# Lattice.net
KiCad netlist of a schematic drawn in EAGLE
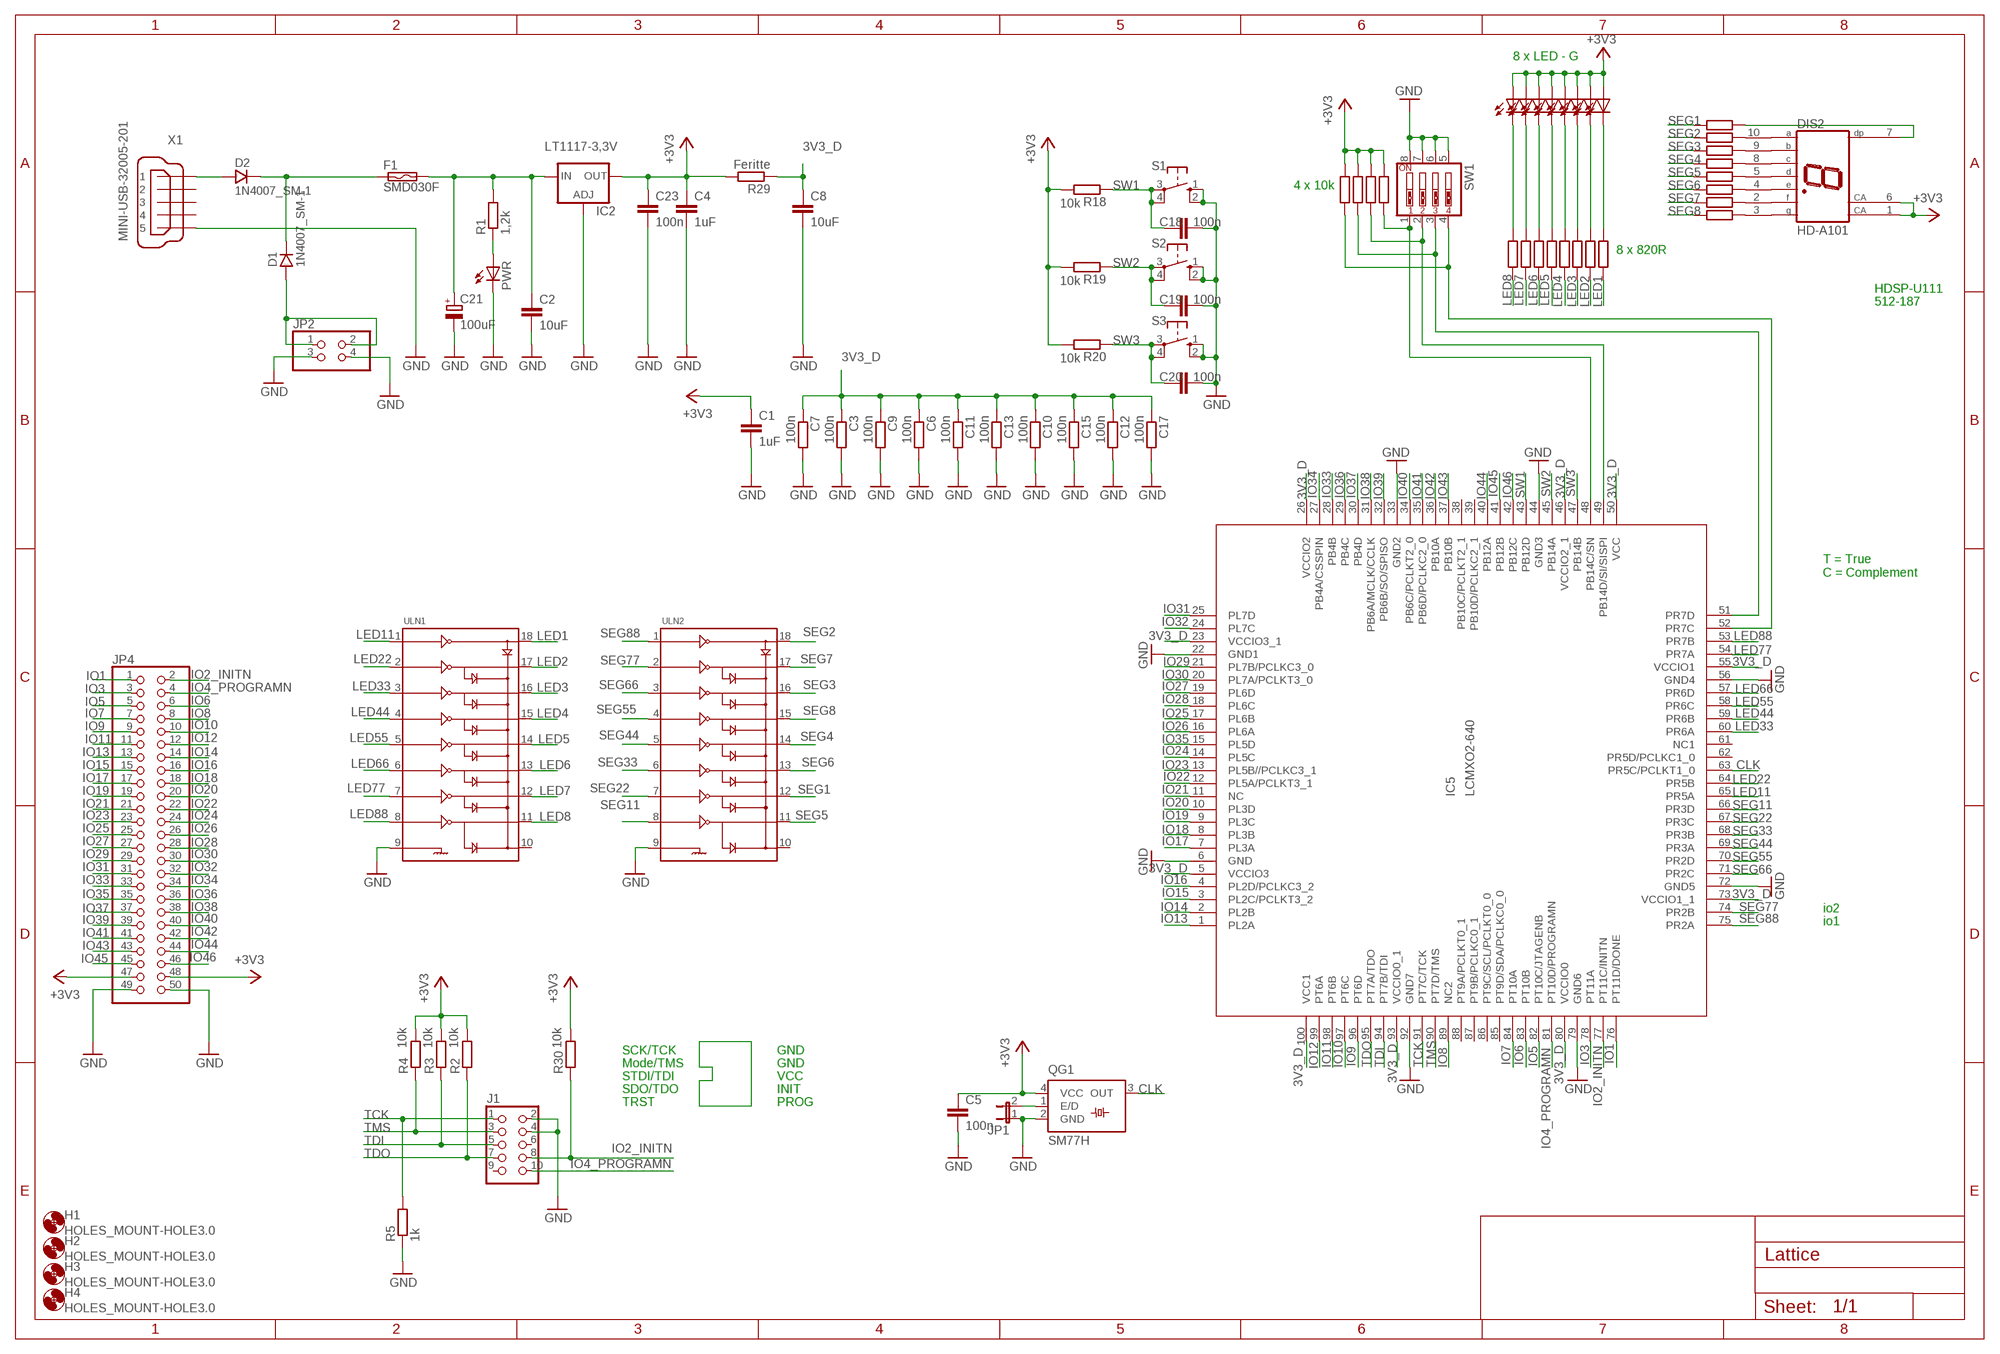
[diagram p0: schematic, sheet 1]

(export (version "E")
  (design (tool "Eeschema 10.0.6"))
  (components
    (comp (ref "C1")
      (value "1uF")
      (footprint "eagle-import:C1206")
      (libsource (lib "eagle-import") (part "C-EUC1206"))
    )
    (comp (ref "C2")
      (value "10uF")
      (footprint "eagle-import:C1206")
      (libsource (lib "eagle-import") (part "C-EUC1206"))
    )
    (comp (ref "C3")
      (value "100n")
      (footprint "eagle-import:R0603")
      (libsource (lib "eagle-import") (part "R-EU_R0603"))
    )
    (comp (ref "C4")
      (value "1uF")
      (footprint "eagle-import:C1206")
      (libsource (lib "eagle-import") (part "C-EUC1206"))
    )
    (comp (ref "C5")
      (value "100n")
      (footprint "eagle-import:C0805")
      (libsource (lib "eagle-import") (part "C-EUC0805"))
    )
    (comp (ref "C6")
      (value "100n")
      (footprint "eagle-import:R0603")
      (libsource (lib "eagle-import") (part "R-EU_R0603"))
    )
    (comp (ref "C7")
      (value "100n")
      (footprint "eagle-import:R0603")
      (libsource (lib "eagle-import") (part "R-EU_R0603"))
    )
    (comp (ref "C8")
      (value "10uF")
      (footprint "eagle-import:C1206")
      (libsource (lib "eagle-import") (part "C-EUC1206"))
    )
    (comp (ref "C9")
      (value "100n")
      (footprint "eagle-import:R0603")
      (libsource (lib "eagle-import") (part "R-EU_R0603"))
    )
    (comp (ref "C10")
      (value "100n")
      (footprint "eagle-import:R0603")
      (libsource (lib "eagle-import") (part "R-EU_R0603"))
    )
    (comp (ref "C11")
      (value "100n")
      (footprint "eagle-import:R0603")
      (libsource (lib "eagle-import") (part "R-EU_R0603"))
    )
    (comp (ref "C12")
      (value "100n")
      (footprint "eagle-import:R0603")
      (libsource (lib "eagle-import") (part "R-EU_R0603"))
    )
    (comp (ref "C13")
      (value "100n")
      (footprint "eagle-import:R0603")
      (libsource (lib "eagle-import") (part "R-EU_R0603"))
    )
    (comp (ref "C15")
      (value "100n")
      (footprint "eagle-import:R0603")
      (libsource (lib "eagle-import") (part "R-EU_R0603"))
    )
    (comp (ref "C17")
      (value "100n")
      (footprint "eagle-import:R0603")
      (libsource (lib "eagle-import") (part "R-EU_R0603"))
    )
    (comp (ref "C18")
      (value "100n")
      (footprint "eagle-import:C0805")
      (libsource (lib "eagle-import") (part "C-EUC0805"))
    )
    (comp (ref "C19")
      (value "100n")
      (footprint "eagle-import:C0805")
      (libsource (lib "eagle-import") (part "C-EUC0805"))
    )
    (comp (ref "C20")
      (value "100n")
      (footprint "eagle-import:C0805")
      (libsource (lib "eagle-import") (part "C-EUC0805"))
    )
    (comp (ref "C21")
      (value "100uF")
      (footprint "eagle-import:153CLV-0605")
      (libsource (lib "eagle-import") (part "CPOL-EU153CLV-0605"))
    )
    (comp (ref "C23")
      (value "100n")
      (footprint "eagle-import:C0805")
      (libsource (lib "eagle-import") (part "C-EUC0805"))
    )
    (comp (ref "D1")
      (value "1N4007_SM-1")
      (footprint "eagle-import:SM-1")
      (libsource (lib "eagle-import") (part "1N4007_SM-1"))
    )
    (comp (ref "D2")
      (value "1N4007_SM-1")
      (footprint "eagle-import:SM-1")
      (libsource (lib "eagle-import") (part "1N4007_SM-1"))
    )
    (comp (ref "DIS2")
      (value "HD-A101")
      (footprint "eagle-import:HDSP-A")
      (libsource (lib "eagle-import") (part "HD-A101"))
    )
    (comp (ref "F1")
      (value "SMD030F")
      (footprint "eagle-import:SMD050F")
      (libsource (lib "eagle-import") (part "SMDF030"))
    )
    (comp (ref "H1")
      (value "HOLES_MOUNT-HOLE3.0")
      (footprint "eagle-import:HOLES_3,0")
      (libsource (lib "eagle-import") (part "HOLES_MOUNT-HOLE3.0"))
    )
    (comp (ref "H2")
      (value "HOLES_MOUNT-HOLE3.0")
      (footprint "eagle-import:HOLES_3,0")
      (libsource (lib "eagle-import") (part "HOLES_MOUNT-HOLE3.0"))
    )
    (comp (ref "H3")
      (value "HOLES_MOUNT-HOLE3.0")
      (footprint "eagle-import:HOLES_3,0")
      (libsource (lib "eagle-import") (part "HOLES_MOUNT-HOLE3.0"))
    )
    (comp (ref "H4")
      (value "HOLES_MOUNT-HOLE3.0")
      (footprint "eagle-import:HOLES_3,0")
      (libsource (lib "eagle-import") (part "HOLES_MOUNT-HOLE3.0"))
    )
    (comp (ref "IC2")
      (value "LT1117-3,3V")
      (footprint "eagle-import:SOT223")
      (libsource (lib "eagle-import") (part "LD117A?S50TR"))
    )
    (comp (ref "IC5")
      (value "LCMXO2-640")
      (footprint "eagle-import:LCMX02-640")
      (libsource (lib "eagle-import") (part "LXMXO2-640"))
    )
    (comp (ref "J1")
      (value "CON_HEADER_2X05-PTH+SHROUDED_A")
      (footprint "eagle-import:PINSHRD_PTH_2X05")
      (libsource (lib "eagle-import") (part "CON_HEADER_2X05-PTH+SHROUDED_A"))
    )
    (comp (ref "JP1")
      (value "JP1E")
      (footprint "eagle-import:JP1")
      (libsource (lib "eagle-import") (part "JP1E"))
    )
    (comp (ref "JP2")
      (value "PINHD-2X2")
      (footprint "eagle-import:2X02")
      (libsource (lib "eagle-import") (part "PINHD-2X2"))
    )
    (comp (ref "JP4")
      (value "PINHD-2X25")
      (footprint "eagle-import:2X25")
      (libsource (lib "eagle-import") (part "PINHD-2X25"))
    )
    (comp (ref "LED1")
      (value "LEDSMT1206")
      (footprint "eagle-import:1206")
      (libsource (lib "eagle-import") (part "LEDSMT1206"))
    )
    (comp (ref "LED2")
      (value "LEDSMT1206")
      (footprint "eagle-import:1206")
      (libsource (lib "eagle-import") (part "LEDSMT1206"))
    )
    (comp (ref "LED3")
      (value "LEDSMT1206")
      (footprint "eagle-import:1206")
      (libsource (lib "eagle-import") (part "LEDSMT1206"))
    )
    (comp (ref "LED4")
      (value "LEDSMT1206")
      (footprint "eagle-import:1206")
      (libsource (lib "eagle-import") (part "LEDSMT1206"))
    )
    (comp (ref "LED5")
      (value "LEDSMT1206")
      (footprint "eagle-import:1206")
      (libsource (lib "eagle-import") (part "LEDSMT1206"))
    )
    (comp (ref "LED6")
      (value "LEDSMT1206")
      (footprint "eagle-import:1206")
      (libsource (lib "eagle-import") (part "LEDSMT1206"))
    )
    (comp (ref "LED7")
      (value "LEDSMT1206")
      (footprint "eagle-import:1206")
      (libsource (lib "eagle-import") (part "LEDSMT1206"))
    )
    (comp (ref "LED8")
      (value "LEDSMT1206")
      (footprint "eagle-import:1206")
      (libsource (lib "eagle-import") (part "LEDSMT1206"))
    )
    (comp (ref "PWR")
      (value "LEDSMT1206")
      (footprint "eagle-import:1206")
      (libsource (lib "eagle-import") (part "LEDSMT1206"))
    )
    (comp (ref "QG1")
      (value "SM77H")
      (footprint "eagle-import:SM77H")
      (libsource (lib "eagle-import") (part "SM77H"))
    )
    (comp (ref "R1")
      (value "1,2k")
      (footprint "eagle-import:R0805")
      (libsource (lib "eagle-import") (part "rcl_R-EU_R0805"))
    )
    (comp (ref "R2")
      (value "10k")
      (footprint "eagle-import:R0805")
      (libsource (lib "eagle-import") (part "rcl_R-EU_R0805"))
    )
    (comp (ref "R3")
      (value "10k")
      (footprint "eagle-import:R0805")
      (libsource (lib "eagle-import") (part "rcl_R-EU_R0805"))
    )
    (comp (ref "R4")
      (value "10k")
      (footprint "eagle-import:R0805")
      (libsource (lib "eagle-import") (part "rcl_R-EU_R0805"))
    )
    (comp (ref "R5")
      (value "1k")
      (footprint "eagle-import:R0805")
      (libsource (lib "eagle-import") (part "rcl_R-EU_R0805"))
    )
    (comp (ref "R6")
      (value "R-EU_R0805")
      (footprint "eagle-import:R0805")
      (libsource (lib "eagle-import") (part "rcl_R-EU_R0805"))
    )
    (comp (ref "R7")
      (value "R-EU_R0805")
      (footprint "eagle-import:R0805")
      (libsource (lib "eagle-import") (part "rcl_R-EU_R0805"))
    )
    (comp (ref "R8")
      (value "R-EU_R0805")
      (footprint "eagle-import:R0805")
      (libsource (lib "eagle-import") (part "rcl_R-EU_R0805"))
    )
    (comp (ref "R9")
      (value "R-EU_R0805")
      (footprint "eagle-import:R0805")
      (libsource (lib "eagle-import") (part "rcl_R-EU_R0805"))
    )
    (comp (ref "R10")
      (value "R-EU_R0805")
      (footprint "eagle-import:R0805")
      (libsource (lib "eagle-import") (part "rcl_R-EU_R0805"))
    )
    (comp (ref "R11")
      (value "R-EU_R0805")
      (footprint "eagle-import:R0805")
      (libsource (lib "eagle-import") (part "rcl_R-EU_R0805"))
    )
    (comp (ref "R12")
      (value "R-EU_R0805")
      (footprint "eagle-import:R0805")
      (libsource (lib "eagle-import") (part "rcl_R-EU_R0805"))
    )
    (comp (ref "R13")
      (value "R-EU_R0805")
      (footprint "eagle-import:R0805")
      (libsource (lib "eagle-import") (part "rcl_R-EU_R0805"))
    )
    (comp (ref "R14")
      (value "R-EU_R0805")
      (footprint "eagle-import:R0805")
      (libsource (lib "eagle-import") (part "rcl_R-EU_R0805"))
    )
    (comp (ref "R15")
      (value "R-EU_R0805")
      (footprint "eagle-import:R0805")
      (libsource (lib "eagle-import") (part "rcl_R-EU_R0805"))
    )
    (comp (ref "R16")
      (value "R-EU_R0805")
      (footprint "eagle-import:R0805")
      (libsource (lib "eagle-import") (part "rcl_R-EU_R0805"))
    )
    (comp (ref "R17")
      (value "R-EU_R0805")
      (footprint "eagle-import:R0805")
      (libsource (lib "eagle-import") (part "rcl_R-EU_R0805"))
    )
    (comp (ref "R18")
      (value "10k")
      (footprint "eagle-import:R0805")
      (libsource (lib "eagle-import") (part "rcl_R-EU_R0805"))
    )
    (comp (ref "R19")
      (value "10k")
      (footprint "eagle-import:R0805")
      (libsource (lib "eagle-import") (part "rcl_R-EU_R0805"))
    )
    (comp (ref "R20")
      (value "10k")
      (footprint "eagle-import:R0805")
      (libsource (lib "eagle-import") (part "rcl_R-EU_R0805"))
    )
    (comp (ref "R21")
      (value "R-EU_R0805")
      (footprint "eagle-import:R0805")
      (libsource (lib "eagle-import") (part "rcl_R-EU_R0805"))
    )
    (comp (ref "R22")
      (value "R-EU_R0805")
      (footprint "eagle-import:R0805")
      (libsource (lib "eagle-import") (part "rcl_R-EU_R0805"))
    )
    (comp (ref "R23")
      (value "R-EU_R0805")
      (footprint "eagle-import:R0805")
      (libsource (lib "eagle-import") (part "rcl_R-EU_R0805"))
    )
    (comp (ref "R24")
      (value "R-EU_R0805")
      (footprint "eagle-import:R0805")
      (libsource (lib "eagle-import") (part "rcl_R-EU_R0805"))
    )
    (comp (ref "R25")
      (value "R-EU_R0805")
      (footprint "eagle-import:R0805")
      (libsource (lib "eagle-import") (part "rcl_R-EU_R0805"))
    )
    (comp (ref "R26")
      (value "R-EU_R0805")
      (footprint "eagle-import:R0805")
      (libsource (lib "eagle-import") (part "rcl_R-EU_R0805"))
    )
    (comp (ref "R27")
      (value "R-EU_R0805")
      (footprint "eagle-import:R0805")
      (libsource (lib "eagle-import") (part "rcl_R-EU_R0805"))
    )
    (comp (ref "R28")
      (value "R-EU_R0805")
      (footprint "eagle-import:R0805")
      (libsource (lib "eagle-import") (part "rcl_R-EU_R0805"))
    )
    (comp (ref "R29")
      (value "Feritte")
      (footprint "eagle-import:R0805")
      (libsource (lib "eagle-import") (part "rcl_R-EU_R0805"))
    )
    (comp (ref "R30")
      (value "10k")
      (footprint "eagle-import:R0805")
      (libsource (lib "eagle-import") (part "rcl_R-EU_R0805"))
    )
    (comp (ref "S1")
      (value "10-XX")
      (footprint "eagle-import:B3F-10XX")
      (fields (field (name "MPN") "B3F-1000"))
      (libsource (lib "eagle-import") (part "10-XX"))
    )
    (comp (ref "S2")
      (value "10-XX")
      (footprint "eagle-import:B3F-10XX")
      (fields (field (name "MPN") "B3F-1000"))
      (libsource (lib "eagle-import") (part "10-XX"))
    )
    (comp (ref "S3")
      (value "10-XX")
      (footprint "eagle-import:B3F-10XX")
      (fields (field (name "MPN") "B3F-1000"))
      (libsource (lib "eagle-import") (part "10-XX"))
    )
    (comp (ref "SW1")
      (value "SW_DIP-4")
      (footprint "eagle-import:EDG-04")
      (libsource (lib "eagle-import") (part "SW_DIP-4"))
    )
    (comp (ref "ULN1")
      (value "ULN2803SOIC")
      (footprint "eagle-import:SO018")
      (libsource (lib "eagle-import") (part "ULN2803SOIC"))
    )
    (comp (ref "ULN2")
      (value "ULN2803SOIC")
      (footprint "eagle-import:SO018")
      (libsource (lib "eagle-import") (part "ULN2803SOIC"))
    )
    (comp (ref "X1")
      (value "MINI-USB-32005-201")
      (footprint "eagle-import:32005-201")
      (libsource (lib "eagle-import") (part "MINI-USB-32005-201"))
    )
  )
  (nets
    (net (code "1") (name "+3V3") (class "Default")
      (node (ref "C1") (pin "1") (pinfunction "1_1") (pintype "passive"))
      (node (ref "C23") (pin "1") (pinfunction "1_1") (pintype "passive"))
      (node (ref "C4") (pin "1") (pinfunction "1_1") (pintype "passive"))
      (node (ref "C5") (pin "1") (pinfunction "1_1") (pintype "passive"))
      (node (ref "DIS2") (pin "1") (pinfunction "CA_1") (pintype "passive"))
      (node (ref "DIS2") (pin "6") (pinfunction "CA_6") (pintype "passive"))
      (node (ref "IC2") (pin "4") (pinfunction "OUT_4") (pintype "passive"))
      (node (ref "JP4") (pin "47") (pinfunction "47_47") (pintype "passive"))
      (node (ref "JP4") (pin "48") (pinfunction "48_48") (pintype "passive"))
      (node (ref "LED1") (pin "A") (pinfunction "A_A") (pintype "passive"))
      (node (ref "LED2") (pin "A") (pinfunction "A_A") (pintype "passive"))
      (node (ref "LED3") (pin "A") (pinfunction "A_A") (pintype "passive"))
      (node (ref "LED4") (pin "A") (pinfunction "A_A") (pintype "passive"))
      (node (ref "LED5") (pin "A") (pinfunction "A_A") (pintype "passive"))
      (node (ref "LED6") (pin "A") (pinfunction "A_A") (pintype "passive"))
      (node (ref "LED7") (pin "A") (pinfunction "A_A") (pintype "passive"))
      (node (ref "LED8") (pin "A") (pinfunction "A_A") (pintype "passive"))
      (node (ref "QG1") (pin "4") (pinfunction "VCC_4") (pintype "power_in"))
      (node (ref "R14") (pin "1") (pinfunction "1_1") (pintype "passive"))
      (node (ref "R15") (pin "1") (pinfunction "1_1") (pintype "passive"))
      (node (ref "R16") (pin "1") (pinfunction "1_1") (pintype "passive"))
      (node (ref "R17") (pin "1") (pinfunction "1_1") (pintype "passive"))
      (node (ref "R18") (pin "2") (pinfunction "2_2") (pintype "passive"))
      (node (ref "R19") (pin "2") (pinfunction "2_2") (pintype "passive"))
      (node (ref "R2") (pin "2") (pinfunction "2_2") (pintype "passive"))
      (node (ref "R20") (pin "2") (pinfunction "2_2") (pintype "passive"))
      (node (ref "R29") (pin "2") (pinfunction "2_2") (pintype "passive"))
      (node (ref "R3") (pin "2") (pinfunction "2_2") (pintype "passive"))
      (node (ref "R30") (pin "2") (pinfunction "2_2") (pintype "passive"))
      (node (ref "R4") (pin "2") (pinfunction "2_2") (pintype "passive"))
    )
    (net (code "2") (name "/3V3_D") (class "Default")
      (node (ref "C10") (pin "1") (pinfunction "1_1") (pintype "passive"))
      (node (ref "C11") (pin "1") (pinfunction "1_1") (pintype "passive"))
      (node (ref "C12") (pin "1") (pinfunction "1_1") (pintype "passive"))
      (node (ref "C13") (pin "1") (pinfunction "1_1") (pintype "passive"))
      (node (ref "C15") (pin "1") (pinfunction "1_1") (pintype "passive"))
      (node (ref "C17") (pin "1") (pinfunction "1_1") (pintype "passive"))
      (node (ref "C3") (pin "1") (pinfunction "1_1") (pintype "passive"))
      (node (ref "C6") (pin "1") (pinfunction "1_1") (pintype "passive"))
      (node (ref "C7") (pin "1") (pinfunction "1_1") (pintype "passive"))
      (node (ref "C8") (pin "1") (pinfunction "1_1") (pintype "passive"))
      (node (ref "C9") (pin "1") (pinfunction "1_1") (pintype "passive"))
      (node (ref "IC5") (pin "100") (pinfunction "VCC1_100") (pintype "power_in"))
      (node (ref "IC5") (pin "23") (pinfunction "VCCIO3_1_23") (pintype "power_in"))
      (node (ref "IC5") (pin "26") (pinfunction "VCCIO2_26") (pintype "power_in"))
      (node (ref "IC5") (pin "46") (pinfunction "VCCIO2_1_46") (pintype "power_in"))
      (node (ref "IC5") (pin "5") (pinfunction "VCCIO3_5") (pintype "power_in"))
      (node (ref "IC5") (pin "50") (pinfunction "VCC_50") (pintype "power_in"))
      (node (ref "IC5") (pin "55") (pinfunction "VCCIO1_55") (pintype "power_in"))
      (node (ref "IC5") (pin "73") (pinfunction "VCCIO1_1_73") (pintype "power_in"))
      (node (ref "IC5") (pin "80") (pinfunction "VCCIO0_80") (pintype "power_in"))
      (node (ref "IC5") (pin "93") (pinfunction "VCCIO0_1_93") (pintype "power_in"))
      (node (ref "R29") (pin "1") (pinfunction "1_1") (pintype "passive"))
    )
    (net (code "3") (name "/CLK") (class "Default")
      (node (ref "IC5") (pin "63") (pinfunction "PR5C/PCLKT1_0_63") (pintype "bidirectional"))
      (node (ref "QG1") (pin "3") (pinfunction "OUT_3") (pintype "output"))
    )
    (net (code "4") (name "/IO1") (class "Default")
      (node (ref "IC5") (pin "76") (pinfunction "PT11D/DONE_76") (pintype "bidirectional"))
      (node (ref "JP4") (pin "1") (pinfunction "1_1") (pintype "passive"))
    )
    (net (code "5") (name "/IO2_INITN") (class "Default")
      (node (ref "IC5") (pin "77") (pinfunction "PT11C/INITN_77") (pintype "bidirectional"))
      (node (ref "J1") (pin "8") (pinfunction "8_8") (pintype "passive"))
      (node (ref "JP4") (pin "2") (pinfunction "2_2") (pintype "passive"))
      (node (ref "R30") (pin "1") (pinfunction "1_1") (pintype "passive"))
    )
    (net (code "6") (name "/IO3") (class "Default")
      (node (ref "IC5") (pin "78") (pinfunction "PT11A_78") (pintype "bidirectional"))
      (node (ref "JP4") (pin "3") (pinfunction "3_3") (pintype "passive"))
    )
    (net (code "7") (name "/IO4_PROGRAMN") (class "Default")
      (node (ref "IC5") (pin "81") (pinfunction "PT10D/PROGRAMN_81") (pintype "bidirectional"))
      (node (ref "J1") (pin "10") (pinfunction "10_10") (pintype "passive"))
      (node (ref "JP4") (pin "4") (pinfunction "4_4") (pintype "passive"))
    )
    (net (code "8") (name "/IO5") (class "Default")
      (node (ref "IC5") (pin "82") (pinfunction "PT10C/JTAGENB_82") (pintype "bidirectional"))
      (node (ref "JP4") (pin "5") (pinfunction "5_5") (pintype "passive"))
    )
    (net (code "9") (name "/IO6") (class "Default")
      (node (ref "IC5") (pin "83") (pinfunction "PT10B_83") (pintype "bidirectional"))
      (node (ref "JP4") (pin "6") (pinfunction "6_6") (pintype "passive"))
    )
    (net (code "10") (name "/IO7") (class "Default")
      (node (ref "IC5") (pin "84") (pinfunction "PT10A_84") (pintype "bidirectional"))
      (node (ref "JP4") (pin "7") (pinfunction "7_7") (pintype "passive"))
    )
    (net (code "11") (name "/IO8") (class "Default")
      (node (ref "IC5") (pin "89") (pinfunction "NC2_89") (pintype "bidirectional"))
      (node (ref "JP4") (pin "8") (pinfunction "8_8") (pintype "passive"))
    )
    (net (code "12") (name "/IO9") (class "Default")
      (node (ref "IC5") (pin "96") (pinfunction "PT6D_96") (pintype "bidirectional"))
      (node (ref "JP4") (pin "9") (pinfunction "9_9") (pintype "passive"))
    )
    (net (code "13") (name "/IO10") (class "Default")
      (node (ref "IC5") (pin "97") (pinfunction "PT6C_97") (pintype "bidirectional"))
      (node (ref "JP4") (pin "10") (pinfunction "10_10") (pintype "passive"))
    )
    (net (code "14") (name "/IO11") (class "Default")
      (node (ref "IC5") (pin "98") (pinfunction "PT6B_98") (pintype "bidirectional"))
      (node (ref "JP4") (pin "11") (pinfunction "11_11") (pintype "passive"))
    )
    (net (code "15") (name "/IO12") (class "Default")
      (node (ref "IC5") (pin "99") (pinfunction "PT6A_99") (pintype "bidirectional"))
      (node (ref "JP4") (pin "12") (pinfunction "12_12") (pintype "passive"))
    )
    (net (code "16") (name "/IO13") (class "Default")
      (node (ref "IC5") (pin "1") (pinfunction "PL2A_1") (pintype "input"))
      (node (ref "JP4") (pin "13") (pinfunction "13_13") (pintype "passive"))
    )
    (net (code "17") (name "/IO14") (class "Default")
      (node (ref "IC5") (pin "2") (pinfunction "PL2B_2") (pintype "bidirectional"))
      (node (ref "JP4") (pin "14") (pinfunction "14_14") (pintype "passive"))
    )
    (net (code "18") (name "/IO15") (class "Default")
      (node (ref "IC5") (pin "3") (pinfunction "PL2C/PCLKT3_2_3") (pintype "bidirectional"))
      (node (ref "JP4") (pin "15") (pinfunction "15_15") (pintype "passive"))
    )
    (net (code "19") (name "/IO16") (class "Default")
      (node (ref "IC5") (pin "4") (pinfunction "PL2D/PCLKC3_2_4") (pintype "bidirectional"))
      (node (ref "JP4") (pin "16") (pinfunction "16_16") (pintype "passive"))
    )
    (net (code "20") (name "/IO17") (class "Default")
      (node (ref "IC5") (pin "7") (pinfunction "PL3A_7") (pintype "bidirectional"))
      (node (ref "JP4") (pin "17") (pinfunction "17_17") (pintype "passive"))
    )
    (net (code "21") (name "/IO18") (class "Default")
      (node (ref "IC5") (pin "8") (pinfunction "PL3B_8") (pintype "bidirectional"))
      (node (ref "JP4") (pin "18") (pinfunction "18_18") (pintype "passive"))
    )
    (net (code "22") (name "/IO19") (class "Default")
      (node (ref "IC5") (pin "9") (pinfunction "PL3C_9") (pintype "bidirectional"))
      (node (ref "JP4") (pin "19") (pinfunction "19_19") (pintype "passive"))
    )
    (net (code "23") (name "/IO20") (class "Default")
      (node (ref "IC5") (pin "10") (pinfunction "PL3D_10") (pintype "bidirectional"))
      (node (ref "JP4") (pin "20") (pinfunction "20_20") (pintype "passive"))
    )
    (net (code "24") (name "/IO21") (class "Default")
      (node (ref "IC5") (pin "11") (pinfunction "NC_11") (pintype "bidirectional"))
      (node (ref "JP4") (pin "21") (pinfunction "21_21") (pintype "passive"))
    )
    (net (code "25") (name "/IO22") (class "Default")
      (node (ref "IC5") (pin "12") (pinfunction "PL5A/PCLKT3_1_12") (pintype "bidirectional"))
      (node (ref "JP4") (pin "22") (pinfunction "22_22") (pintype "passive"))
    )
    (net (code "26") (name "/IO23") (class "Default")
      (node (ref "IC5") (pin "13") (pinfunction "PL5B//PCLKC3_1_13") (pintype "bidirectional"))
      (node (ref "JP4") (pin "23") (pinfunction "23_23") (pintype "passive"))
    )
    (net (code "27") (name "/IO24") (class "Default")
      (node (ref "IC5") (pin "14") (pinfunction "PL5C_14") (pintype "bidirectional"))
      (node (ref "JP4") (pin "24") (pinfunction "24_24") (pintype "passive"))
    )
    (net (code "28") (name "/IO25") (class "Default")
      (node (ref "IC5") (pin "17") (pinfunction "PL6B_17") (pintype "bidirectional"))
      (node (ref "JP4") (pin "25") (pinfunction "25_25") (pintype "passive"))
    )
    (net (code "29") (name "/IO26") (class "Default")
      (node (ref "IC5") (pin "16") (pinfunction "PL6A_16") (pintype "bidirectional"))
      (node (ref "JP4") (pin "26") (pinfunction "26_26") (pintype "passive"))
    )
    (net (code "30") (name "/IO27") (class "Default")
      (node (ref "IC5") (pin "19") (pinfunction "PL6D_19") (pintype "bidirectional"))
      (node (ref "JP4") (pin "27") (pinfunction "27_27") (pintype "passive"))
    )
    (net (code "31") (name "/IO28") (class "Default")
      (node (ref "IC5") (pin "18") (pinfunction "PL6C_18") (pintype "bidirectional"))
      (node (ref "JP4") (pin "28") (pinfunction "28_28") (pintype "passive"))
    )
    (net (code "32") (name "/IO29") (class "Default")
      (node (ref "IC5") (pin "21") (pinfunction "PL7B/PCLKC3_0_21") (pintype "bidirectional"))
      (node (ref "JP4") (pin "29") (pinfunction "29_29") (pintype "passive"))
    )
    (net (code "33") (name "/IO30") (class "Default")
      (node (ref "IC5") (pin "20") (pinfunction "PL7A/PCLKT3_0_20") (pintype "bidirectional"))
      (node (ref "JP4") (pin "30") (pinfunction "30_30") (pintype "passive"))
    )
    (net (code "34") (name "/IO31") (class "Default")
      (node (ref "IC5") (pin "25") (pinfunction "PL7D_25") (pintype "bidirectional"))
      (node (ref "JP4") (pin "31") (pinfunction "31_31") (pintype "passive"))
    )
    (net (code "35") (name "/IO32") (class "Default")
      (node (ref "IC5") (pin "24") (pinfunction "PL7C_24") (pintype "bidirectional"))
      (node (ref "JP4") (pin "32") (pinfunction "32_32") (pintype "passive"))
    )
    (net (code "36") (name "/IO33") (class "Default")
      (node (ref "IC5") (pin "28") (pinfunction "PB4B_28") (pintype "bidirectional"))
      (node (ref "JP4") (pin "33") (pinfunction "33_33") (pintype "passive"))
    )
    (net (code "37") (name "/IO34") (class "Default")
      (node (ref "IC5") (pin "27") (pinfunction "PB4A/CSSPIN_27") (pintype "bidirectional"))
      (node (ref "JP4") (pin "34") (pinfunction "34_34") (pintype "passive"))
    )
    (net (code "38") (name "/IO35") (class "Default")
      (node (ref "IC5") (pin "15") (pinfunction "PL5D_15") (pintype "bidirectional"))
      (node (ref "JP4") (pin "35") (pinfunction "35_35") (pintype "passive"))
    )
    (net (code "39") (name "/IO36") (class "Default")
      (node (ref "IC5") (pin "29") (pinfunction "PB4C_29") (pintype "bidirectional"))
      (node (ref "JP4") (pin "36") (pinfunction "36_36") (pintype "passive"))
    )
    (net (code "40") (name "/IO37") (class "Default")
      (node (ref "IC5") (pin "30") (pinfunction "PB4D_30") (pintype "bidirectional"))
      (node (ref "JP4") (pin "37") (pinfunction "37_37") (pintype "passive"))
    )
    (net (code "41") (name "/IO38") (class "Default")
      (node (ref "IC5") (pin "31") (pinfunction "PB6A/MCLK/CCLK_31") (pintype "bidirectional"))
      (node (ref "JP4") (pin "38") (pinfunction "38_38") (pintype "passive"))
    )
    (net (code "42") (name "/IO39") (class "Default")
      (node (ref "IC5") (pin "32") (pinfunction "PB6B/SO/SPISO_32") (pintype "bidirectional"))
      (node (ref "JP4") (pin "39") (pinfunction "39_39") (pintype "passive"))
    )
    (net (code "43") (name "/IO40") (class "Default")
      (node (ref "IC5") (pin "34") (pinfunction "PB6C/PCLKT2_0_34") (pintype "bidirectional"))
      (node (ref "JP4") (pin "40") (pinfunction "40_40") (pintype "passive"))
    )
    (net (code "44") (name "/IO41") (class "Default")
      (node (ref "IC5") (pin "35") (pinfunction "PB6D/PCLKC2_0_35") (pintype "bidirectional"))
      (node (ref "JP4") (pin "41") (pinfunction "41_41") (pintype "passive"))
    )
    (net (code "45") (name "/IO42") (class "Default")
      (node (ref "IC5") (pin "36") (pinfunction "PB10A_36") (pintype "bidirectional"))
      (node (ref "JP4") (pin "42") (pinfunction "42_42") (pintype "passive"))
    )
    (net (code "46") (name "/IO43") (class "Default")
      (node (ref "IC5") (pin "37") (pinfunction "PB10B_37") (pintype "bidirectional"))
      (node (ref "JP4") (pin "43") (pinfunction "43_43") (pintype "passive"))
    )
    (net (code "47") (name "/IO44") (class "Default")
      (node (ref "IC5") (pin "40") (pinfunction "PB12A_40") (pintype "bidirectional"))
      (node (ref "JP4") (pin "44") (pinfunction "44_44") (pintype "passive"))
    )
    (net (code "48") (name "/IO45") (class "Default")
      (node (ref "IC5") (pin "41") (pinfunction "PB12B_41") (pintype "bidirectional"))
      (node (ref "JP4") (pin "45") (pinfunction "45_45") (pintype "passive"))
    )
    (net (code "49") (name "/IO46") (class "Default")
      (node (ref "IC5") (pin "42") (pinfunction "PB12C_42") (pintype "bidirectional"))
      (node (ref "JP4") (pin "46") (pinfunction "46_46") (pintype "passive"))
    )
    (net (code "50") (name "/LED1") (class "Default")
      (node (ref "R6") (pin "1") (pinfunction "1_1") (pintype "passive"))
      (node (ref "ULN1") (pin "18") (pinfunction "18_18") (pintype "bidirectional"))
    )
    (net (code "51") (name "/LED2") (class "Default")
      (node (ref "R7") (pin "1") (pinfunction "1_1") (pintype "passive"))
      (node (ref "ULN1") (pin "17") (pinfunction "17_17") (pintype "bidirectional"))
    )
    (net (code "52") (name "/LED3") (class "Default")
      (node (ref "R8") (pin "1") (pinfunction "1_1") (pintype "passive"))
      (node (ref "ULN1") (pin "16") (pinfunction "16_16") (pintype "bidirectional"))
    )
    (net (code "53") (name "/LED4") (class "Default")
      (node (ref "R9") (pin "1") (pinfunction "1_1") (pintype "passive"))
      (node (ref "ULN1") (pin "15") (pinfunction "15_15") (pintype "bidirectional"))
    )
    (net (code "54") (name "/LED5") (class "Default")
      (node (ref "R10") (pin "1") (pinfunction "1_1") (pintype "passive"))
      (node (ref "ULN1") (pin "14") (pinfunction "14_14") (pintype "bidirectional"))
    )
    (net (code "55") (name "/LED6") (class "Default")
      (node (ref "R11") (pin "1") (pinfunction "1_1") (pintype "passive"))
      (node (ref "ULN1") (pin "13") (pinfunction "13_13") (pintype "bidirectional"))
    )
    (net (code "56") (name "/LED7") (class "Default")
      (node (ref "R12") (pin "1") (pinfunction "1_1") (pintype "passive"))
      (node (ref "ULN1") (pin "12") (pinfunction "12_12") (pintype "bidirectional"))
    )
    (net (code "57") (name "/LED8") (class "Default")
      (node (ref "R13") (pin "1") (pinfunction "1_1") (pintype "passive"))
      (node (ref "ULN1") (pin "11") (pinfunction "11_11") (pintype "bidirectional"))
    )
    (net (code "58") (name "/LED11") (class "Default")
      (node (ref "IC5") (pin "65") (pinfunction "PR5A_65") (pintype "bidirectional"))
      (node (ref "ULN1") (pin "1") (pinfunction "1_1") (pintype "bidirectional"))
    )
    (net (code "59") (name "/LED22") (class "Default")
      (node (ref "IC5") (pin "64") (pinfunction "PR5B_64") (pintype "bidirectional"))
      (node (ref "ULN1") (pin "2") (pinfunction "2_2") (pintype "bidirectional"))
    )
    (net (code "60") (name "/LED33") (class "Default")
      (node (ref "IC5") (pin "60") (pinfunction "PR6A_60") (pintype "bidirectional"))
      (node (ref "ULN1") (pin "3") (pinfunction "3_3") (pintype "bidirectional"))
    )
    (net (code "61") (name "/LED44") (class "Default")
      (node (ref "IC5") (pin "59") (pinfunction "PR6B_59") (pintype "bidirectional"))
      (node (ref "ULN1") (pin "4") (pinfunction "4_4") (pintype "bidirectional"))
    )
    (net (code "62") (name "/LED55") (class "Default")
      (node (ref "IC5") (pin "58") (pinfunction "PR6C_58") (pintype "bidirectional"))
      (node (ref "ULN1") (pin "5") (pinfunction "5_5") (pintype "bidirectional"))
    )
    (net (code "63") (name "/LED66") (class "Default")
      (node (ref "IC5") (pin "57") (pinfunction "PR6D_57") (pintype "bidirectional"))
      (node (ref "ULN1") (pin "6") (pinfunction "6_6") (pintype "bidirectional"))
    )
    (net (code "64") (name "/LED77") (class "Default")
      (node (ref "IC5") (pin "54") (pinfunction "PR7A_54") (pintype "bidirectional"))
      (node (ref "ULN1") (pin "7") (pinfunction "7_7") (pintype "bidirectional"))
    )
    (net (code "65") (name "/LED88") (class "Default")
      (node (ref "IC5") (pin "53") (pinfunction "PR7B_53") (pintype "bidirectional"))
      (node (ref "ULN1") (pin "8") (pinfunction "8_8") (pintype "bidirectional"))
    )
    (net (code "66") (name "/SEG1") (class "Default")
      (node (ref "R21") (pin "2") (pinfunction "2_2") (pintype "passive"))
      (node (ref "ULN2") (pin "12") (pinfunction "12_12") (pintype "bidirectional"))
    )
    (net (code "67") (name "/SEG2") (class "Default")
      (node (ref "R22") (pin "2") (pinfunction "2_2") (pintype "passive"))
      (node (ref "ULN2") (pin "18") (pinfunction "18_18") (pintype "bidirectional"))
    )
    (net (code "68") (name "/SEG3") (class "Default")
      (node (ref "R23") (pin "2") (pinfunction "2_2") (pintype "passive"))
      (node (ref "ULN2") (pin "16") (pinfunction "16_16") (pintype "bidirectional"))
    )
    (net (code "69") (name "/SEG4") (class "Default")
      (node (ref "R24") (pin "2") (pinfunction "2_2") (pintype "passive"))
      (node (ref "ULN2") (pin "14") (pinfunction "14_14") (pintype "bidirectional"))
    )
    (net (code "70") (name "/SEG5") (class "Default")
      (node (ref "R25") (pin "2") (pinfunction "2_2") (pintype "passive"))
      (node (ref "ULN2") (pin "11") (pinfunction "11_11") (pintype "bidirectional"))
    )
    (net (code "71") (name "/SEG6") (class "Default")
      (node (ref "R26") (pin "2") (pinfunction "2_2") (pintype "passive"))
      (node (ref "ULN2") (pin "13") (pinfunction "13_13") (pintype "bidirectional"))
    )
    (net (code "72") (name "/SEG7") (class "Default")
      (node (ref "R27") (pin "2") (pinfunction "2_2") (pintype "passive"))
      (node (ref "ULN2") (pin "17") (pinfunction "17_17") (pintype "bidirectional"))
    )
    (net (code "73") (name "/SEG8") (class "Default")
      (node (ref "R28") (pin "2") (pinfunction "2_2") (pintype "passive"))
      (node (ref "ULN2") (pin "15") (pinfunction "15_15") (pintype "bidirectional"))
    )
    (net (code "74") (name "/SEG11") (class "Default")
      (node (ref "IC5") (pin "66") (pinfunction "PR3D_66") (pintype "bidirectional"))
      (node (ref "ULN2") (pin "8") (pinfunction "8_8") (pintype "bidirectional"))
    )
    (net (code "75") (name "/SEG22") (class "Default")
      (node (ref "IC5") (pin "67") (pinfunction "PR3C_67") (pintype "bidirectional"))
      (node (ref "ULN2") (pin "7") (pinfunction "7_7") (pintype "bidirectional"))
    )
    (net (code "76") (name "/SEG33") (class "Default")
      (node (ref "IC5") (pin "68") (pinfunction "PR3B_68") (pintype "bidirectional"))
      (node (ref "ULN2") (pin "6") (pinfunction "6_6") (pintype "bidirectional"))
    )
    (net (code "77") (name "/SEG44") (class "Default")
      (node (ref "IC5") (pin "69") (pinfunction "PR3A_69") (pintype "bidirectional"))
      (node (ref "ULN2") (pin "5") (pinfunction "5_5") (pintype "bidirectional"))
    )
    (net (code "78") (name "/SEG55") (class "Default")
      (node (ref "IC5") (pin "70") (pinfunction "PR2D_70") (pintype "bidirectional"))
      (node (ref "ULN2") (pin "4") (pinfunction "4_4") (pintype "bidirectional"))
    )
    (net (code "79") (name "/SEG66") (class "Default")
      (node (ref "IC5") (pin "71") (pinfunction "PR2C_71") (pintype "bidirectional"))
      (node (ref "ULN2") (pin "3") (pinfunction "3_3") (pintype "bidirectional"))
    )
    (net (code "80") (name "/SEG77") (class "Default")
      (node (ref "IC5") (pin "74") (pinfunction "PR2B_74") (pintype "bidirectional"))
      (node (ref "ULN2") (pin "2") (pinfunction "2_2") (pintype "bidirectional"))
    )
    (net (code "81") (name "/SEG88") (class "Default")
      (node (ref "IC5") (pin "75") (pinfunction "PR2A_75") (pintype "bidirectional"))
      (node (ref "ULN2") (pin "1") (pinfunction "1_1") (pintype "bidirectional"))
    )
    (net (code "82") (name "/SW1") (class "Default")
      (node (ref "C18") (pin "1") (pinfunction "1_1") (pintype "passive"))
      (node (ref "IC5") (pin "43") (pinfunction "PB12D_43") (pintype "bidirectional"))
      (node (ref "R18") (pin "1") (pinfunction "1_1") (pintype "passive"))
      (node (ref "S1") (pin "3") (pinfunction "P_3") (pintype "passive"))
      (node (ref "S1") (pin "4") (pinfunction "P1_4") (pintype "passive"))
    )
    (net (code "83") (name "/SW2") (class "Default")
      (node (ref "C19") (pin "1") (pinfunction "1_1") (pintype "passive"))
      (node (ref "IC5") (pin "45") (pinfunction "PB14A_45") (pintype "bidirectional"))
      (node (ref "R19") (pin "1") (pinfunction "1_1") (pintype "passive"))
      (node (ref "S2") (pin "3") (pinfunction "P_3") (pintype "passive"))
      (node (ref "S2") (pin "4") (pinfunction "P1_4") (pintype "passive"))
    )
    (net (code "84") (name "/SW3") (class "Default")
      (node (ref "C20") (pin "1") (pinfunction "1_1") (pintype "passive"))
      (node (ref "IC5") (pin "47") (pinfunction "PB14B_47") (pintype "bidirectional"))
      (node (ref "R20") (pin "1") (pinfunction "1_1") (pintype "passive"))
      (node (ref "S3") (pin "3") (pinfunction "P_3") (pintype "passive"))
      (node (ref "S3") (pin "4") (pinfunction "P1_4") (pintype "passive"))
    )
    (net (code "85") (name "/TCK") (class "Default")
      (node (ref "IC5") (pin "91") (pinfunction "PT7C/TCK_91") (pintype "bidirectional"))
      (node (ref "J1") (pin "1") (pinfunction "1_1") (pintype "passive"))
      (node (ref "R5") (pin "2") (pinfunction "2_2") (pintype "passive"))
    )
    (net (code "86") (name "/TDI") (class "Default")
      (node (ref "IC5") (pin "94") (pinfunction "PT7B/TDI_94") (pintype "bidirectional"))
      (node (ref "J1") (pin "5") (pinfunction "5_5") (pintype "passive"))
      (node (ref "R3") (pin "1") (pinfunction "1_1") (pintype "passive"))
    )
    (net (code "87") (name "/TDO") (class "Default")
      (node (ref "IC5") (pin "95") (pinfunction "PT7A/TDO_95") (pintype "bidirectional"))
      (node (ref "J1") (pin "7") (pinfunction "7_7") (pintype "passive"))
      (node (ref "R2") (pin "1") (pinfunction "1_1") (pintype "passive"))
    )
    (net (code "88") (name "/TMS") (class "Default")
      (node (ref "IC5") (pin "90") (pinfunction "PT7D/TMS_90") (pintype "bidirectional"))
      (node (ref "J1") (pin "3") (pinfunction "3_3") (pintype "passive"))
      (node (ref "R4") (pin "1") (pinfunction "1_1") (pintype "passive"))
    )
    (net (code "89") (name "GND") (class "Default")
      (node (ref "C1") (pin "2") (pinfunction "2_2") (pintype "passive"))
      (node (ref "C10") (pin "2") (pinfunction "2_2") (pintype "passive"))
      (node (ref "C11") (pin "2") (pinfunction "2_2") (pintype "passive"))
      (node (ref "C12") (pin "2") (pinfunction "2_2") (pintype "passive"))
      (node (ref "C13") (pin "2") (pinfunction "2_2") (pintype "passive"))
      (node (ref "C15") (pin "2") (pinfunction "2_2") (pintype "passive"))
      (node (ref "C17") (pin "2") (pinfunction "2_2") (pintype "passive"))
      (node (ref "C18") (pin "2") (pinfunction "2_2") (pintype "passive"))
      (node (ref "C19") (pin "2") (pinfunction "2_2") (pintype "passive"))
      (node (ref "C2") (pin "2") (pinfunction "2_2") (pintype "passive"))
      (node (ref "C20") (pin "2") (pinfunction "2_2") (pintype "passive"))
      (node (ref "C21") (pin "-") (pinfunction "-_-") (pintype "passive"))
      (node (ref "C23") (pin "2") (pinfunction "2_2") (pintype "passive"))
      (node (ref "C3") (pin "2") (pinfunction "2_2") (pintype "passive"))
      (node (ref "C4") (pin "2") (pinfunction "2_2") (pintype "passive"))
      (node (ref "C5") (pin "2") (pinfunction "2_2") (pintype "passive"))
      (node (ref "C6") (pin "2") (pinfunction "2_2") (pintype "passive"))
      (node (ref "C7") (pin "2") (pinfunction "2_2") (pintype "passive"))
      (node (ref "C8") (pin "2") (pinfunction "2_2") (pintype "passive"))
      (node (ref "C9") (pin "2") (pinfunction "2_2") (pintype "passive"))
      (node (ref "IC2") (pin "1") (pinfunction "ADJ_1") (pintype "input"))
      (node (ref "IC5") (pin "22") (pinfunction "GND1_22") (pintype "power_in"))
      (node (ref "IC5") (pin "33") (pinfunction "GND2_33") (pintype "power_in"))
      (node (ref "IC5") (pin "44") (pinfunction "GND3_44") (pintype "power_in"))
      (node (ref "IC5") (pin "56") (pinfunction "GND4_56") (pintype "power_in"))
      (node (ref "IC5") (pin "6") (pinfunction "GND_6") (pintype "power_in"))
      (node (ref "IC5") (pin "72") (pinfunction "GND5_72") (pintype "power_in"))
      (node (ref "IC5") (pin "79") (pinfunction "GND6_79") (pintype "power_in"))
      (node (ref "IC5") (pin "92") (pinfunction "GND7_92") (pintype "power_in"))
      (node (ref "J1") (pin "2") (pinfunction "2_2") (pintype "passive"))
      (node (ref "J1") (pin "4") (pinfunction "4_4") (pintype "passive"))
      (node (ref "JP1") (pin "1") (pinfunction "1_1") (pintype "passive"))
      (node (ref "JP2") (pin "3") (pinfunction "3_3") (pintype "passive"))
      (node (ref "JP2") (pin "4") (pinfunction "4_4") (pintype "passive"))
      (node (ref "JP4") (pin "49") (pinfunction "49_49") (pintype "passive"))
      (node (ref "JP4") (pin "50") (pinfunction "50_50") (pintype "passive"))
      (node (ref "PWR") (pin "C") (pinfunction "C_C") (pintype "passive"))
      (node (ref "QG1") (pin "2") (pinfunction "GND_2") (pintype "power_in"))
      (node (ref "R5") (pin "1") (pinfunction "1_1") (pintype "passive"))
      (node (ref "S1") (pin "1") (pinfunction "S_1") (pintype "passive"))
      (node (ref "S1") (pin "2") (pinfunction "S1_2") (pintype "passive"))
      (node (ref "S2") (pin "1") (pinfunction "S_1") (pintype "passive"))
      (node (ref "S2") (pin "2") (pinfunction "S1_2") (pintype "passive"))
      (node (ref "S3") (pin "1") (pinfunction "S_1") (pintype "passive"))
      (node (ref "S3") (pin "2") (pinfunction "S1_2") (pintype "passive"))
      (node (ref "SW1") (pin "5") (pinfunction "5_5") (pintype "passive"))
      (node (ref "SW1") (pin "6") (pinfunction "6_6") (pintype "passive"))
      (node (ref "SW1") (pin "7") (pinfunction "7_7") (pintype "passive"))
      (node (ref "SW1") (pin "8") (pinfunction "8_8") (pintype "passive"))
      (node (ref "ULN1") (pin "9") (pinfunction "9_9") (pintype "bidirectional"))
      (node (ref "ULN2") (pin "9") (pinfunction "9_9") (pintype "bidirectional"))
      (node (ref "X1") (pin "5") (pinfunction "5_5") (pintype "passive"))
    )
    (net (code "90") (name "Net-(D1-PadA)") (class "Default")
      (node (ref "D1") (pin "A") (pinfunction "A_A") (pintype "passive"))
      (node (ref "JP2") (pin "1") (pinfunction "1_1") (pintype "passive"))
      (node (ref "JP2") (pin "2") (pinfunction "2_2") (pintype "passive"))
    )
    (net (code "91") (name "Net-(D1-PadK)") (class "Default")
      (node (ref "D1") (pin "K") (pinfunction "K_K") (pintype "passive"))
      (node (ref "D2") (pin "K") (pinfunction "K_K") (pintype "passive"))
      (node (ref "F1") (pin "1") (pinfunction "1_1") (pintype "passive"))
    )
    (net (code "92") (name "Net-(D2-PadA)") (class "Default")
      (node (ref "D2") (pin "A") (pinfunction "A_A") (pintype "passive"))
      (node (ref "X1") (pin "1") (pinfunction "1_1") (pintype "passive"))
    )
    (net (code "93") (name "Net-(DIS2-A)") (class "Default")
      (node (ref "DIS2") (pin "10") (pinfunction "A_10") (pintype "passive"))
      (node (ref "R22") (pin "1") (pinfunction "1_1") (pintype "passive"))
    )
    (net (code "94") (name "Net-(DIS2-B)") (class "Default")
      (node (ref "DIS2") (pin "9") (pinfunction "B_9") (pintype "passive"))
      (node (ref "R23") (pin "1") (pinfunction "1_1") (pintype "passive"))
    )
    (net (code "95") (name "Net-(DIS2-C)") (class "Default")
      (node (ref "DIS2") (pin "8") (pinfunction "C_8") (pintype "passive"))
      (node (ref "R24") (pin "1") (pinfunction "1_1") (pintype "passive"))
    )
    (net (code "96") (name "Net-(DIS2-D)") (class "Default")
      (node (ref "DIS2") (pin "5") (pinfunction "D_5") (pintype "passive"))
      (node (ref "R25") (pin "1") (pinfunction "1_1") (pintype "passive"))
    )
    (net (code "97") (name "Net-(DIS2-DP)") (class "Default")
      (node (ref "DIS2") (pin "7") (pinfunction "DP_7") (pintype "passive"))
      (node (ref "R21") (pin "1") (pinfunction "1_1") (pintype "passive"))
    )
    (net (code "98") (name "Net-(DIS2-E)") (class "Default")
      (node (ref "DIS2") (pin "4") (pinfunction "E_4") (pintype "passive"))
      (node (ref "R26") (pin "1") (pinfunction "1_1") (pintype "passive"))
    )
    (net (code "99") (name "Net-(DIS2-F)") (class "Default")
      (node (ref "DIS2") (pin "2") (pinfunction "F_2") (pintype "passive"))
      (node (ref "R27") (pin "1") (pinfunction "1_1") (pintype "passive"))
    )
    (net (code "100") (name "Net-(DIS2-G)") (class "Default")
      (node (ref "DIS2") (pin "3") (pinfunction "G_3") (pintype "passive"))
      (node (ref "R28") (pin "1") (pinfunction "1_1") (pintype "passive"))
    )
    (net (code "101") (name "Net-(IC2-IN)") (class "Default")
      (node (ref "C2") (pin "1") (pinfunction "1_1") (pintype "passive"))
      (node (ref "C21") (pin "+") (pinfunction "+_+") (pintype "passive"))
      (node (ref "F1") (pin "2") (pinfunction "2_2") (pintype "passive"))
      (node (ref "IC2") (pin "3") (pinfunction "IN_3") (pintype "input"))
      (node (ref "R1") (pin "2") (pinfunction "2_2") (pintype "passive"))
    )
    (net (code "102") (name "Net-(IC5-PB14C{slash}SN)") (class "Default")
      (node (ref "IC5") (pin "48") (pinfunction "PB14C/SN_48") (pintype "bidirectional"))
      (node (ref "R14") (pin "2") (pinfunction "2_2") (pintype "passive"))
      (node (ref "SW1") (pin "1") (pinfunction "1_1") (pintype "passive"))
    )
    (net (code "103") (name "Net-(IC5-PB14D{slash}SI{slash}SISPI)") (class "Default")
      (node (ref "IC5") (pin "49") (pinfunction "PB14D/SI/SISPI_49") (pintype "bidirectional"))
      (node (ref "R15") (pin "2") (pinfunction "2_2") (pintype "passive"))
      (node (ref "SW1") (pin "2") (pinfunction "2_2") (pintype "passive"))
    )
    (net (code "104") (name "Net-(IC5-PR7C)") (class "Default")
      (node (ref "IC5") (pin "52") (pinfunction "PR7C_52") (pintype "bidirectional"))
      (node (ref "R17") (pin "2") (pinfunction "2_2") (pintype "passive"))
      (node (ref "SW1") (pin "4") (pinfunction "4_4") (pintype "passive"))
    )
    (net (code "105") (name "Net-(IC5-PR7D)") (class "Default")
      (node (ref "IC5") (pin "51") (pinfunction "PR7D_51") (pintype "bidirectional"))
      (node (ref "R16") (pin "2") (pinfunction "2_2") (pintype "passive"))
      (node (ref "SW1") (pin "3") (pinfunction "3_3") (pintype "passive"))
    )
    (net (code "106") (name "Net-(LED1-PadC)") (class "Default")
      (node (ref "LED1") (pin "C") (pinfunction "C_C") (pintype "passive"))
      (node (ref "R13") (pin "2") (pinfunction "2_2") (pintype "passive"))
    )
    (net (code "107") (name "Net-(LED2-PadC)") (class "Default")
      (node (ref "LED2") (pin "C") (pinfunction "C_C") (pintype "passive"))
      (node (ref "R12") (pin "2") (pinfunction "2_2") (pintype "passive"))
    )
    (net (code "108") (name "Net-(LED3-PadC)") (class "Default")
      (node (ref "LED3") (pin "C") (pinfunction "C_C") (pintype "passive"))
      (node (ref "R11") (pin "2") (pinfunction "2_2") (pintype "passive"))
    )
    (net (code "109") (name "Net-(LED4-PadC)") (class "Default")
      (node (ref "LED4") (pin "C") (pinfunction "C_C") (pintype "passive"))
      (node (ref "R10") (pin "2") (pinfunction "2_2") (pintype "passive"))
    )
    (net (code "110") (name "Net-(LED5-PadC)") (class "Default")
      (node (ref "LED5") (pin "C") (pinfunction "C_C") (pintype "passive"))
      (node (ref "R9") (pin "2") (pinfunction "2_2") (pintype "passive"))
    )
    (net (code "111") (name "Net-(LED6-PadC)") (class "Default")
      (node (ref "LED6") (pin "C") (pinfunction "C_C") (pintype "passive"))
      (node (ref "R8") (pin "2") (pinfunction "2_2") (pintype "passive"))
    )
    (net (code "112") (name "Net-(LED7-PadC)") (class "Default")
      (node (ref "LED7") (pin "C") (pinfunction "C_C") (pintype "passive"))
      (node (ref "R7") (pin "2") (pinfunction "2_2") (pintype "passive"))
    )
    (net (code "113") (name "Net-(LED8-PadC)") (class "Default")
      (node (ref "LED8") (pin "C") (pinfunction "C_C") (pintype "passive"))
      (node (ref "R6") (pin "2") (pinfunction "2_2") (pintype "passive"))
    )
    (net (code "114") (name "Net-(PWR-PadA)") (class "Default")
      (node (ref "PWR") (pin "A") (pinfunction "A_A") (pintype "passive"))
      (node (ref "R1") (pin "1") (pinfunction "1_1") (pintype "passive"))
    )
    (net (code "115") (name "Net-(QG1-E{slash}D)") (class "Default")
      (node (ref "JP1") (pin "2") (pinfunction "2_2") (pintype "passive"))
      (node (ref "QG1") (pin "1") (pinfunction "E/D_1") (pintype "input"))
    )
    (net (code "116") (name "unconnected-(IC5-NC1-Pad61)") (class "Default")
      (node (ref "IC5") (pin "61") (pinfunction "NC1_61") (pintype "bidirectional"))
    )
    (net (code "117") (name "unconnected-(IC5-PB10C{slash}PCLKT2_1-Pad38)") (class "Default")
      (node (ref "IC5") (pin "38") (pinfunction "PB10C/PCLKT2_1_38") (pintype "bidirectional"))
    )
    (net (code "118") (name "unconnected-(IC5-PB10D{slash}PCLKC2_1-Pad39)") (class "Default")
      (node (ref "IC5") (pin "39") (pinfunction "PB10D/PCLKC2_1_39") (pintype "bidirectional"))
    )
    (net (code "119") (name "unconnected-(IC5-PR5D{slash}PCLKC1_0-Pad62)") (class "Default")
      (node (ref "IC5") (pin "62") (pinfunction "PR5D/PCLKC1_0_62") (pintype "bidirectional"))
    )
    (net (code "120") (name "unconnected-(IC5-PT9A{slash}PCLKT0_1-Pad88)") (class "Default")
      (node (ref "IC5") (pin "88") (pinfunction "PT9A/PCLKT0_1_88") (pintype "bidirectional"))
    )
    (net (code "121") (name "unconnected-(IC5-PT9B{slash}PCLKC0_1-Pad87)") (class "Default")
      (node (ref "IC5") (pin "87") (pinfunction "PT9B/PCLKC0_1_87") (pintype "bidirectional"))
    )
    (net (code "122") (name "unconnected-(IC5-PT9C{slash}SCL{slash}PCLKT0_0-Pad86)") (class "Default")
      (node (ref "IC5") (pin "86") (pinfunction "PT9C/SCL/PCLKT0_0_86") (pintype "bidirectional"))
    )
    (net (code "123") (name "unconnected-(IC5-PT9D{slash}SDA{slash}PCLKC0_0-Pad85)") (class "Default")
      (node (ref "IC5") (pin "85") (pinfunction "PT9D/SDA/PCLKC0_0_85") (pintype "bidirectional"))
    )
    (net (code "124") (name "unconnected-(J1-Pad6)") (class "Default")
      (node (ref "J1") (pin "6") (pinfunction "6_6") (pintype "passive"))
    )
    (net (code "125") (name "unconnected-(J1-Pad9)") (class "Default")
      (node (ref "J1") (pin "9") (pinfunction "9_9") (pintype "passive"))
    )
    (net (code "126") (name "unconnected-(ULN1-Pad10)") (class "Default")
      (node (ref "ULN1") (pin "10") (pinfunction "10_10") (pintype "bidirectional"))
    )
    (net (code "127") (name "unconnected-(ULN2-Pad10)") (class "Default")
      (node (ref "ULN2") (pin "10") (pinfunction "10_10") (pintype "bidirectional"))
    )
    (net (code "128") (name "unconnected-(X1-Pad2)") (class "Default")
      (node (ref "X1") (pin "2") (pinfunction "2_2") (pintype "passive"))
    )
    (net (code "129") (name "unconnected-(X1-Pad3)") (class "Default")
      (node (ref "X1") (pin "3") (pinfunction "3_3") (pintype "passive"))
    )
    (net (code "130") (name "unconnected-(X1-Pad4)") (class "Default")
      (node (ref "X1") (pin "4") (pinfunction "4_4") (pintype "passive"))
    )
  )
)
